# Battery_Charger_Li-Po_1_Cell_6Vin_MCP738.net
KiCad netlist of a schematic drawn in Altium Designer
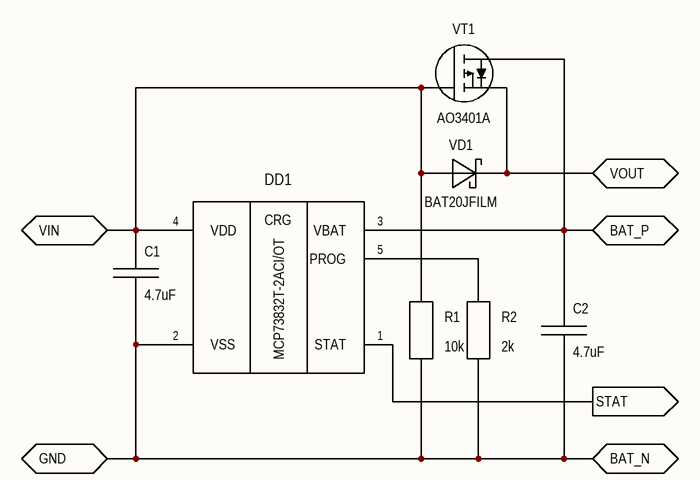
[diagram p0: Battery Charger Li-Po 1 Cell 6Vin MCP73831.SchDoc]

(export (version "E")
  (design (tool "Eeschema 10.0.6"))
  (components
    (comp (ref "C1")
      (value "4.7uF")
      (footprint "CAPC1608L")
      (description "Capacitor Ceramic 4.7uF 6.3V 0603(1608)")
      (fields (field (name "TOLERANCE") "±10%") (field (name "VOLTAGE") "6.3V"))
      (libsource (lib "Capacitors") (part "Capacitor Ceramic 4.7uF 6.3V 0603(1608)"))
    )
    (comp (ref "C2")
      (value "4.7uF")
      (footprint "CAPC1608L")
      (description "Capacitor Ceramic 4.7uF 6.3V 0603(1608)")
      (fields (field (name "TOLERANCE") "±10%") (field (name "VOLTAGE") "6.3V"))
      (libsource (lib "Capacitors") (part "Capacitor Ceramic 4.7uF 6.3V 0603(1608)"))
    )
    (comp (ref "DD1")
      (value "MCP73832T-2ACI/OT")
      (footprint "SOT-23-5")
      (description "Battery Charger Li-ion/Li Polymer")
      (fields (field (name "MANUFACTURER") "Microchip Technology"))
      (libsource (lib "Power") (part "MCP73832T-2ACI/OT"))
    )
    (comp (ref "R1")
      (value "10k")
      (footprint "RESC1608L")
      (description "Resistor Ceramic 10k 0.1W 0603(1608)")
      (fields (field (name "TOLERANCE") "±5%") (field (name "POWER") "0.1W"))
      (libsource (lib "Resistors") (part "Resistor Ceramic 10k 0.1W 0603(1608)"))
    )
    (comp (ref "R2")
      (value "2k")
      (footprint "RESC1608L")
      (description "Resistor Ceramic 2k 0.1W 0603(1608)")
      (fields (field (name "TOLERANCE") "±5%") (field (name "POWER") "0.1W"))
      (libsource (lib "Resistors") (part "Resistor Ceramic 2k 0.1W 0603(1608)"))
    )
    (comp (ref "VD1")
      (value "BAT20JFILM")
      (footprint "SOD-323L")
      (description "Diode Schottky 1A 23V (620mV/1A)")
      (fields (field (name "MANUFACTURER") "STMicroelectronics"))
      (libsource (lib "Discrete components") (part "BAT20JFILM"))
    )
    (comp (ref "VT1")
      (value "AO3401A")
      (footprint "SOT-23")
      (description "MOSFET P 4A 30V")
      (fields (field (name "MANUFACTURER") "Alpha & Omega Semiconductor"))
      (libsource (lib "Discrete components") (part "AO3401A"))
    )
  )
  (nets
    (net (code "1") (name "/BAT_N") (class "Default")
      (node (ref "C1") (pin "2") (pinfunction "2_2") (pintype "passive"))
      (node (ref "C2") (pin "2") (pinfunction "2_2") (pintype "passive"))
      (node (ref "DD1") (pin "2") (pinfunction "VSS_2") (pintype "passive"))
      (node (ref "R1") (pin "2") (pinfunction "2_2") (pintype "passive"))
      (node (ref "R2") (pin "2") (pinfunction "2_2") (pintype "passive"))
    )
    (net (code "2") (name "/BAT_P") (class "Default")
      (node (ref "C2") (pin "1") (pinfunction "1_1") (pintype "passive"))
      (node (ref "DD1") (pin "3") (pinfunction "VBAT_3") (pintype "passive"))
      (node (ref "VT1") (pin "3") (pinfunction "Drain_3") (pintype "passive"))
    )
    (net (code "3") (name "/STAT") (class "Default")
      (node (ref "DD1") (pin "1") (pinfunction "STAT_1") (pintype "passive"))
    )
    (net (code "4") (name "/VIN") (class "Default")
      (node (ref "C1") (pin "1") (pinfunction "1_1") (pintype "passive"))
      (node (ref "DD1") (pin "4") (pinfunction "VDD_4") (pintype "passive"))
      (node (ref "R1") (pin "1") (pinfunction "1_1") (pintype "passive"))
      (node (ref "VD1") (pin "1") (pinfunction "Anode_1") (pintype "passive"))
      (node (ref "VT1") (pin "1") (pinfunction "Gate_1") (pintype "passive"))
    )
    (net (code "5") (name "/VOUT") (class "Default")
      (node (ref "VD1") (pin "2") (pinfunction "Cathode_2") (pintype "passive"))
      (node (ref "VT1") (pin "2") (pinfunction "Source_2") (pintype "passive"))
    )
    (net (code "6") (name "Net-(DD1-PROG)") (class "Default")
      (node (ref "DD1") (pin "5") (pinfunction "PROG_5") (pintype "passive"))
      (node (ref "R2") (pin "1") (pinfunction "1_1") (pintype "passive"))
    )
  )
)
